# ETH_PCIE_CTRL.net
KiCad netlist of a schematic drawn in Altium Designer
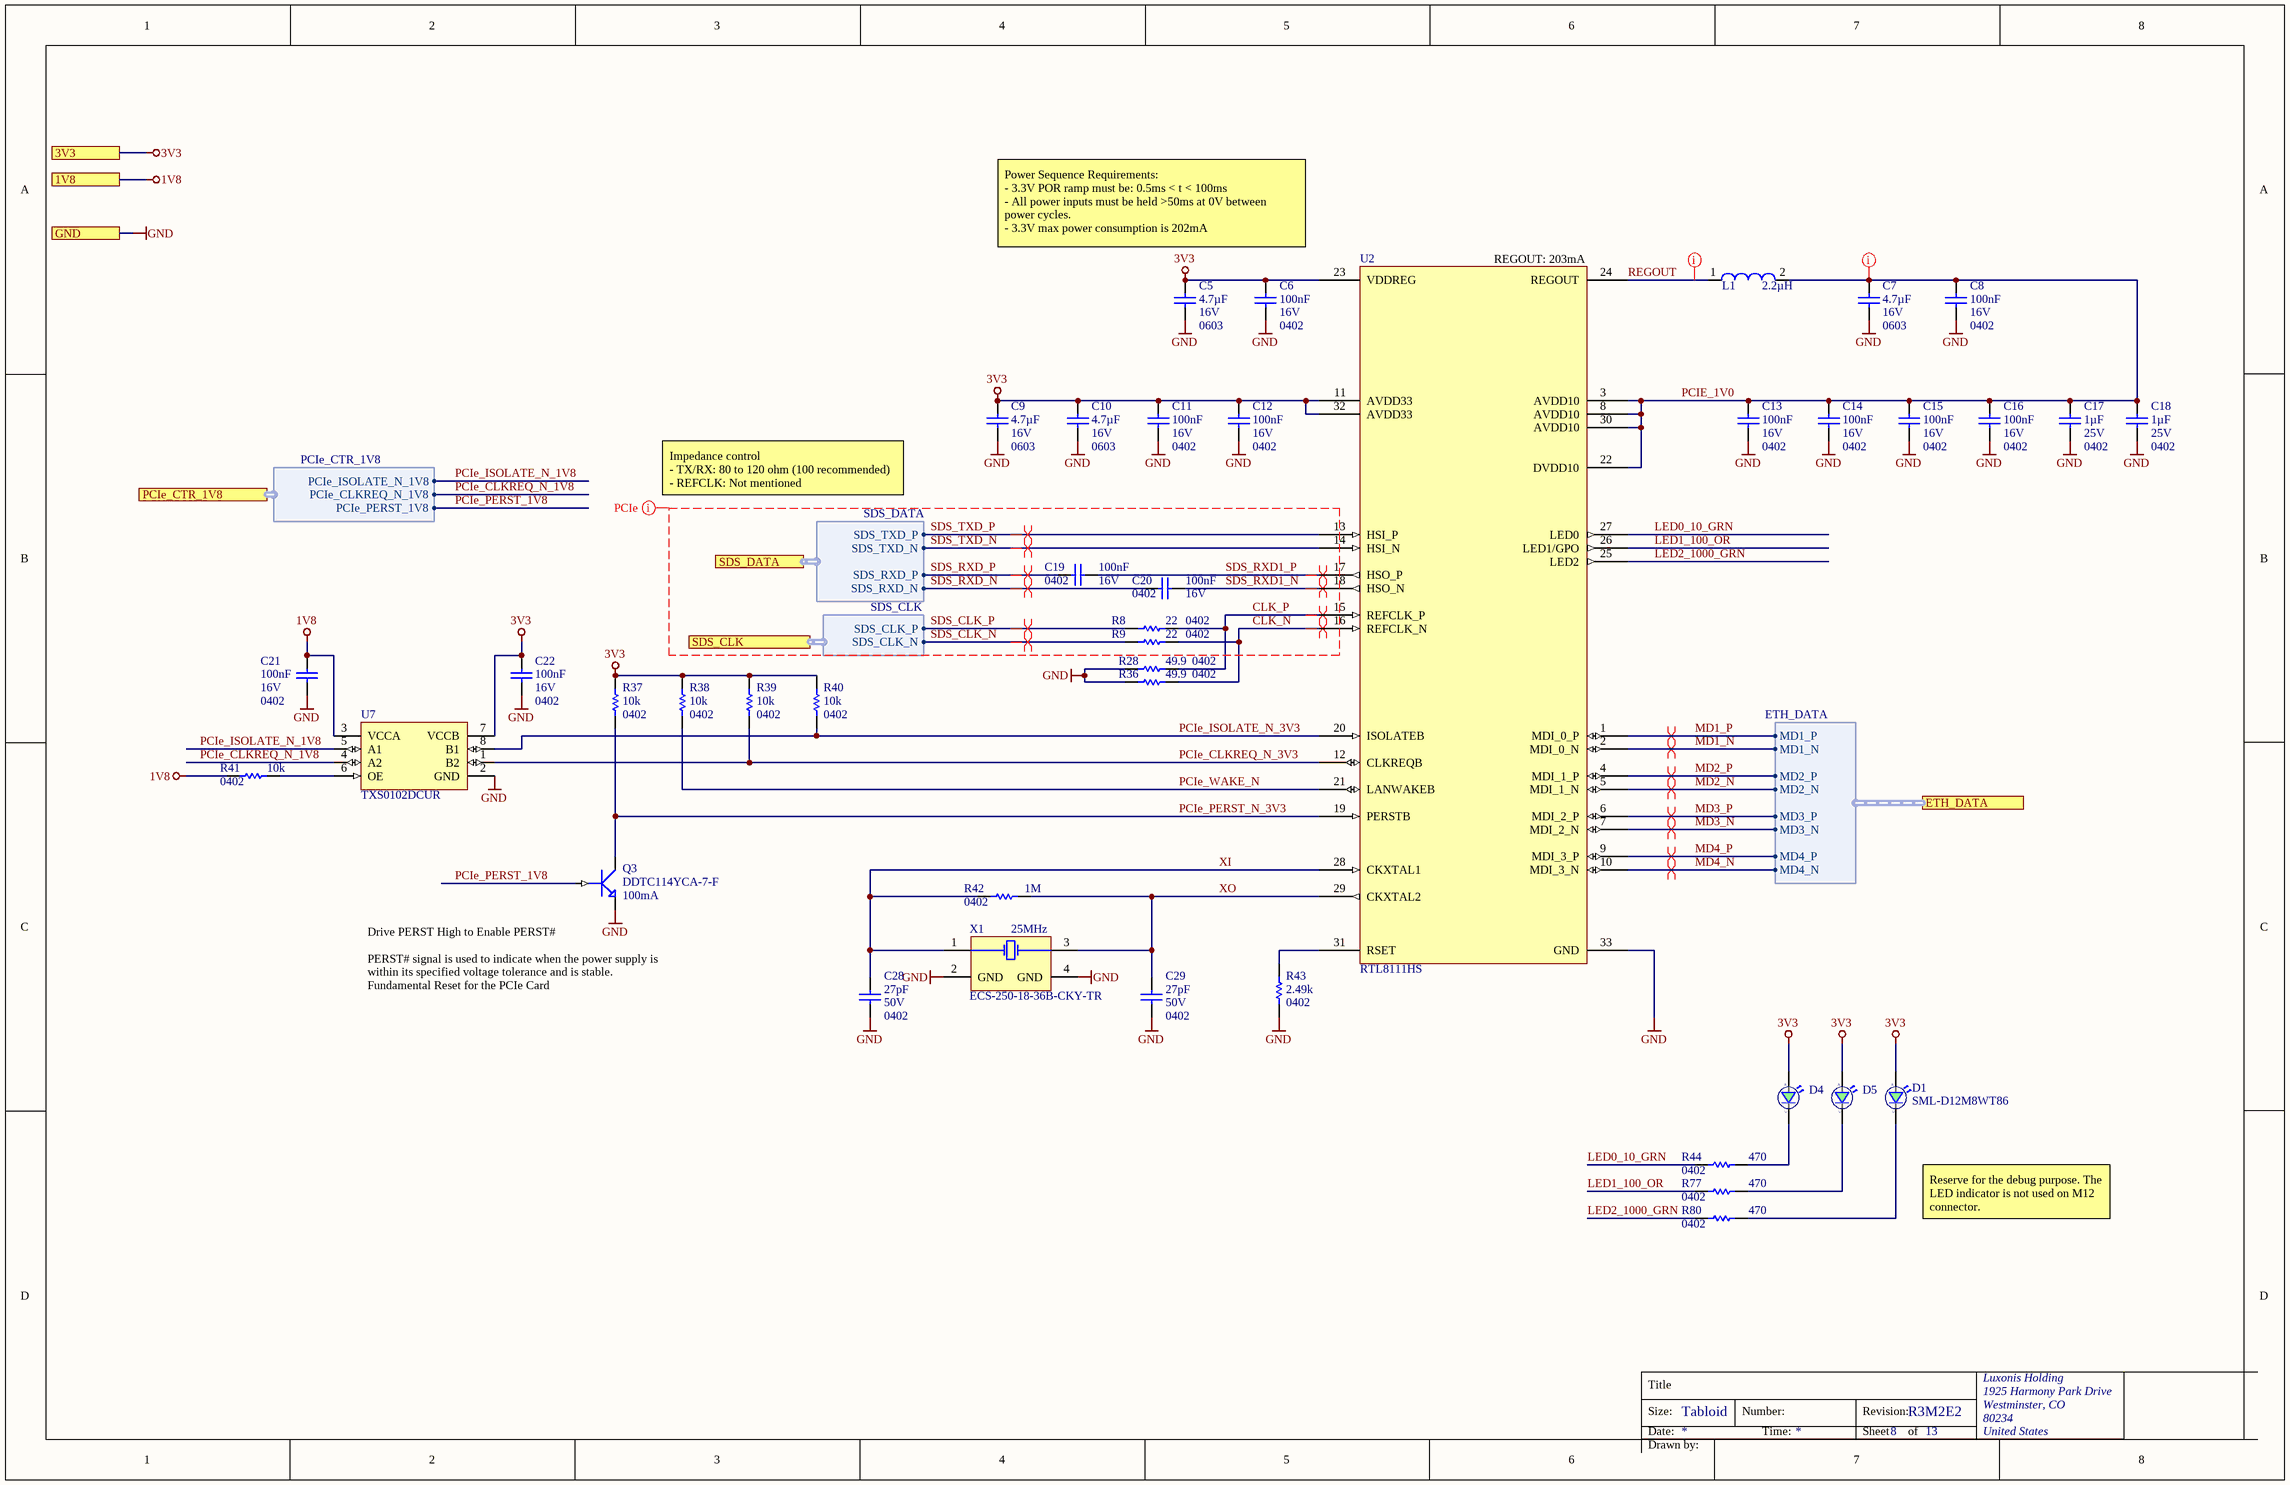
[diagram p0: ETH_PCIE_CTRL.SchDoc]

(export (version "E")
  (design (tool "Eeschema 10.0.6"))
  (components
    (comp (ref "C5")
      (value "4.7µF")
      (footprint "CAPC0603(1608)100_L")
      (description "CAP CER 4.7UF 16V X5R 0603 10%")
      (fields
        (field (name "VOLTAGE RATING") "16V")
        (field (name "CASE/PACKAGE") "0603")
        (field (name "TOLERANCE") "10%")
        (field (name "Comment") "GRM188R61C475KAAJD")
      )
      (libsource (lib "Luxonis LLC") (part "LLL153C70G474ME17E"))
    )
    (comp (ref "C6")
      (value "100nF")
      (footprint "CAPC0402(1005)60_L")
      (description "CAP CER 0.1UF 16V X7R 0402 10%")
      (fields
        (field (name "VOLTAGE RATING") "16V")
        (field (name "CASE/PACKAGE") "0402")
        (field (name "TOLERANCE") "10%")
        (field (name "Comment") "CL05B104KO5NFNC")
      )
      (libsource (lib "Luxonis LLC") (part "GRM188R61C475KAAJD"))
    )
    (comp (ref "C7")
      (value "4.7µF")
      (footprint "CAPC0603(1608)100_L")
      (description "CAP CER 4.7UF 16V X5R 0603 10%")
      (fields
        (field (name "VOLTAGE RATING") "16V")
        (field (name "CASE/PACKAGE") "0603")
        (field (name "TOLERANCE") "10%")
        (field (name "Comment") "GRM188R61C475KAAJD")
      )
      (libsource (lib "Luxonis LLC") (part "LLL153C70G474ME17E"))
    )
    (comp (ref "C8")
      (value "100nF")
      (footprint "CAPC0402(1005)60_L")
      (description "CAP CER 0.1UF 16V X7R 0402 10%")
      (fields
        (field (name "VOLTAGE RATING") "16V")
        (field (name "CASE/PACKAGE") "0402")
        (field (name "TOLERANCE") "10%")
        (field (name "Comment") "CL05B104KO5NFNC")
      )
      (libsource (lib "Luxonis LLC") (part "GRM188R61C475KAAJD"))
    )
    (comp (ref "C9")
      (value "4.7µF")
      (footprint "CAPC0603(1608)100_L")
      (description "CAP CER 4.7UF 16V X5R 0603 10%")
      (fields
        (field (name "VOLTAGE RATING") "16V")
        (field (name "CASE/PACKAGE") "0603")
        (field (name "TOLERANCE") "10%")
        (field (name "Comment") "GRM188R61C475KAAJD")
      )
      (libsource (lib "Luxonis LLC") (part "LLL153C70G474ME17E"))
    )
    (comp (ref "C10")
      (value "4.7µF")
      (footprint "CAPC0603(1608)100_L")
      (description "CAP CER 4.7UF 16V X5R 0603 10%")
      (fields
        (field (name "VOLTAGE RATING") "16V")
        (field (name "CASE/PACKAGE") "0603")
        (field (name "TOLERANCE") "10%")
        (field (name "Comment") "GRM188R61C475KAAJD")
      )
      (libsource (lib "Luxonis LLC") (part "LLL153C70G474ME17E"))
    )
    (comp (ref "C11")
      (value "100nF")
      (footprint "CAPC0402(1005)60_L")
      (description "CAP CER 0.1UF 16V X7R 0402 10%")
      (fields
        (field (name "VOLTAGE RATING") "16V")
        (field (name "CASE/PACKAGE") "0402")
        (field (name "TOLERANCE") "10%")
        (field (name "Comment") "CL05B104KO5NFNC")
      )
      (libsource (lib "Luxonis LLC") (part "GRM188R61C475KAAJD"))
    )
    (comp (ref "C12")
      (value "100nF")
      (footprint "CAPC0402(1005)60_L")
      (description "CAP CER 0.1UF 16V X7R 0402 10%")
      (fields
        (field (name "VOLTAGE RATING") "16V")
        (field (name "CASE/PACKAGE") "0402")
        (field (name "TOLERANCE") "10%")
        (field (name "Comment") "CL05B104KO5NFNC")
      )
      (libsource (lib "Luxonis LLC") (part "GRM188R61C475KAAJD"))
    )
    (comp (ref "C13")
      (value "100nF")
      (footprint "CAPC0402(1005)60_L")
      (description "CAP CER 0.1UF 16V X7R 0402 10%")
      (fields
        (field (name "VOLTAGE RATING") "16V")
        (field (name "CASE/PACKAGE") "0402")
        (field (name "TOLERANCE") "10%")
        (field (name "Comment") "CL05B104KO5NFNC")
      )
      (libsource (lib "Luxonis LLC") (part "GRM188R61C475KAAJD"))
    )
    (comp (ref "C14")
      (value "100nF")
      (footprint "CAPC0402(1005)60_L")
      (description "CAP CER 0.1UF 16V X7R 0402 10%")
      (fields
        (field (name "VOLTAGE RATING") "16V")
        (field (name "CASE/PACKAGE") "0402")
        (field (name "TOLERANCE") "10%")
        (field (name "Comment") "CL05B104KO5NFNC")
      )
      (libsource (lib "Luxonis LLC") (part "GRM188R61C475KAAJD"))
    )
    (comp (ref "C15")
      (value "100nF")
      (footprint "CAPC0402(1005)60_L")
      (description "CAP CER 0.1UF 16V X7R 0402 10%")
      (fields
        (field (name "VOLTAGE RATING") "16V")
        (field (name "CASE/PACKAGE") "0402")
        (field (name "TOLERANCE") "10%")
        (field (name "Comment") "CL05B104KO5NFNC")
      )
      (libsource (lib "Luxonis LLC") (part "GRM188R61C475KAAJD"))
    )
    (comp (ref "C16")
      (value "100nF")
      (footprint "CAPC0402(1005)60_L")
      (description "CAP CER 0.1UF 16V X7R 0402 10%")
      (fields
        (field (name "VOLTAGE RATING") "16V")
        (field (name "CASE/PACKAGE") "0402")
        (field (name "TOLERANCE") "10%")
        (field (name "Comment") "CL05B104KO5NFNC")
      )
      (libsource (lib "Luxonis LLC") (part "GRM188R61C475KAAJD"))
    )
    (comp (ref "C17")
      (value "1µF")
      (footprint "CAPC0402(1005)70_L")
      (description "CAP CER 1UF 25V X5R 0402 10%")
      (fields
        (field (name "VOLTAGE RATING") "25V")
        (field (name "CASE/PACKAGE") "0402")
        (field (name "TOLERANCE") "10%")
        (field (name "Comment") "GRM155R61E105KA12D")
      )
      (libsource (lib "Luxonis LLC") (part "GRM188R61C475KAAJD"))
    )
    (comp (ref "C18")
      (value "1µF")
      (footprint "CAPC0402(1005)70_L")
      (description "CAP CER 1UF 25V X5R 0402 10%")
      (fields
        (field (name "VOLTAGE RATING") "25V")
        (field (name "CASE/PACKAGE") "0402")
        (field (name "TOLERANCE") "10%")
        (field (name "Comment") "GRM155R61E105KA12D")
      )
      (libsource (lib "Luxonis LLC") (part "GRM188R61C475KAAJD"))
    )
    (comp (ref "C19")
      (value "100nF")
      (footprint "CAPC0402(1005)60_L")
      (description "CAP CER 0.1UF 16V X7R 0402 10%")
      (fields
        (field (name "VOLTAGE RATING") "16V")
        (field (name "CASE/PACKAGE") "0402")
        (field (name "TOLERANCE") "10%")
        (field (name "Comment") "CL05B104KO5NFNC")
      )
      (libsource (lib "Luxonis LLC") (part "GRM188R61C475KAAJD"))
    )
    (comp (ref "C20")
      (value "100nF")
      (footprint "CAPC0402(1005)60_L")
      (description "CAP CER 0.1UF 16V X7R 0402 10%")
      (fields
        (field (name "VOLTAGE RATING") "16V")
        (field (name "CASE/PACKAGE") "0402")
        (field (name "TOLERANCE") "10%")
        (field (name "Comment") "CL05B104KO5NFNC")
      )
      (libsource (lib "Luxonis LLC") (part "GRM188R61C475KAAJD"))
    )
    (comp (ref "C21")
      (value "100nF")
      (footprint "CAPC0402(1005)60_L")
      (description "CAP CER 0.1UF 16V X7R 0402 10%")
      (fields
        (field (name "VOLTAGE RATING") "16V")
        (field (name "CASE/PACKAGE") "0402")
        (field (name "TOLERANCE") "10%")
        (field (name "Comment") "CL05B104KO5NFNC")
      )
      (libsource (lib "Luxonis LLC") (part "GRM188R61C475KAAJD"))
    )
    (comp (ref "C22")
      (value "100nF")
      (footprint "CAPC0402(1005)60_L")
      (description "CAP CER 0.1UF 16V X7R 0402 10%")
      (fields
        (field (name "VOLTAGE RATING") "16V")
        (field (name "CASE/PACKAGE") "0402")
        (field (name "TOLERANCE") "10%")
        (field (name "Comment") "CL05B104KO5NFNC")
      )
      (libsource (lib "Luxonis LLC") (part "GRM188R61C475KAAJD"))
    )
    (comp (ref "C28")
      (value "27pF")
      (footprint "CAPC0402(1005)60_L")
      (description "CAP CER 27PF 50V C0G 0402 5%")
      (fields
        (field (name "VOLTAGE RATING") "50V")
        (field (name "TOLERANCE") "5%")
        (field (name "CASE/PACKAGE") "0402")
        (field (name "Comment") "C0402C270J5GACTU")
      )
      (libsource (lib "Luxonis LLC") (part "GRM188R61C475KAAJD"))
    )
    (comp (ref "C29")
      (value "27pF")
      (footprint "CAPC0402(1005)60_L")
      (description "CAP CER 27PF 50V C0G 0402 5%")
      (fields
        (field (name "VOLTAGE RATING") "50V")
        (field (name "TOLERANCE") "5%")
        (field (name "CASE/PACKAGE") "0402")
        (field (name "Comment") "C0402C270J5GACTU")
      )
      (libsource (lib "Luxonis LLC") (part "GRM188R61C475KAAJD"))
    )
    (comp (ref "D1")
      (value "SML-D12M8WT86")
      (footprint "SML_D1xx8W")
      (description "LED GREEN DIFFUSED 0603 SMD Green 572nm LED Indication - Discrete 2.2V 0603 (1608 Metric)")
      (libsource (lib "Luxonis LLC") (part "SML-D12M8WT86"))
    )
    (comp (ref "D4")
      (value "SML-D12M8WT86")
      (footprint "SML_D1xx8W")
      (description "LED GREEN DIFFUSED 0603 SMD Green 572nm LED Indication - Discrete 2.2V 0603 (1608 Metric)")
      (libsource (lib "Luxonis LLC") (part "SML-D12M8WT86"))
    )
    (comp (ref "D5")
      (value "SML-D12M8WT86")
      (footprint "SML_D1xx8W")
      (description "LED GREEN DIFFUSED 0603 SMD Green 572nm LED Indication - Discrete 2.2V 0603 (1608 Metric)")
      (libsource (lib "Luxonis LLC") (part "SML-D12M8WT86"))
    )
    (comp (ref "L1")
      (value "2.2µH")
      (footprint "LQH32NH2R2J23L")
      (description "Inductor Power Chip Wirewound 2.2uH 20% 100KHz Ferrite 1.6A 0.078Ohm DCR 1210 T/R")
      (fields (field (name "TOLERANCE") "20%") (field (name "Comment") "BRL3225T2R2M"))
      (libsource (lib "Luxonis LLC") (part "DFE252012P-1R0M=P2"))
    )
    (comp (ref "Q3")
      (value "DDTC114YCA-7-F")
      (footprint "DDTC114YCA-7-F-Footprint-1")
      (description "TRANS PREBIAS NPN 200MW SOT23-3")
      (fields (field (name "CONTINUOUS DRAIN CURRENT") "100mA"))
      (libsource (lib "Luxonis LLC") (part "DDTC114YCA-7-F"))
    )
    (comp (ref "R8")
      (value "22")
      (footprint "RESC0402(1005)_L")
      (description "RES SMD 22 OHM 1% 1/16W 0402")
      (fields
        (field (name "CASE/PACKAGE") "0402")
        (field (name "TOLERANCE") "1%")
        (field (name "Comment") "RC0402FR-0722RL")
      )
      (libsource (lib "Luxonis LLC") (part "Default resistor symbol"))
    )
    (comp (ref "R9")
      (value "22")
      (footprint "RESC0402(1005)_L")
      (description "RES SMD 22 OHM 1% 1/16W 0402")
      (fields
        (field (name "CASE/PACKAGE") "0402")
        (field (name "TOLERANCE") "1%")
        (field (name "Comment") "RC0402FR-0722RL")
      )
      (libsource (lib "Luxonis LLC") (part "Default resistor symbol"))
    )
    (comp (ref "R28")
      (value "49.9")
      (footprint "RESC0402(1005)_L")
      (description "RES SMD 49.9 OHM 1% 1/16W 0402")
      (fields
        (field (name "TOLERANCE") "1%")
        (field (name "CASE/PACKAGE") "0402")
        (field (name "Comment") "RC0402FR-0749R9L")
      )
      (libsource (lib "Luxonis LLC") (part "RC0402FR-0722RL_1"))
    )
    (comp (ref "R36")
      (value "49.9")
      (footprint "RESC0402(1005)_L")
      (description "RES SMD 49.9 OHM 1% 1/16W 0402")
      (fields
        (field (name "TOLERANCE") "1%")
        (field (name "CASE/PACKAGE") "0402")
        (field (name "Comment") "RC0402FR-0749R9L")
      )
      (libsource (lib "Luxonis LLC") (part "RC0402FR-0722RL_1"))
    )
    (comp (ref "R37")
      (value "10k")
      (footprint "RESC0402(1005)_L")
      (description "RES SMD 10K OHM 1% 1/16W 0402")
      (fields
        (field (name "CASE/PACKAGE") "0402")
        (field (name "TOLERANCE") "1%")
        (field (name "Comment") "RC0402FR-1310KL")
      )
      (libsource (lib "Luxonis LLC") (part "RC0402FR-0722RL_1"))
    )
    (comp (ref "R38")
      (value "10k")
      (footprint "RESC0402(1005)_L")
      (description "RES SMD 10K OHM 1% 1/16W 0402")
      (fields
        (field (name "CASE/PACKAGE") "0402")
        (field (name "TOLERANCE") "1%")
        (field (name "Comment") "RC0402FR-1310KL")
      )
      (libsource (lib "Luxonis LLC") (part "RC0402FR-0722RL_1"))
    )
    (comp (ref "R39")
      (value "10k")
      (footprint "RESC0402(1005)_L")
      (description "RES SMD 10K OHM 1% 1/16W 0402")
      (fields
        (field (name "CASE/PACKAGE") "0402")
        (field (name "TOLERANCE") "1%")
        (field (name "Comment") "RC0402FR-1310KL")
      )
      (libsource (lib "Luxonis LLC") (part "RC0402FR-0722RL_1"))
    )
    (comp (ref "R40")
      (value "10k")
      (footprint "RESC0402(1005)_L")
      (description "RES SMD 10K OHM 1% 1/16W 0402")
      (fields
        (field (name "CASE/PACKAGE") "0402")
        (field (name "TOLERANCE") "1%")
        (field (name "Comment") "RC0402FR-1310KL")
      )
      (libsource (lib "Luxonis LLC") (part "RC0402FR-0722RL_1"))
    )
    (comp (ref "R41")
      (value "10k")
      (footprint "RESC0402(1005)_L")
      (description "RES SMD 10K OHM 1% 1/16W 0402")
      (fields
        (field (name "CASE/PACKAGE") "0402")
        (field (name "TOLERANCE") "1%")
        (field (name "Comment") "RC0402FR-1310KL")
      )
      (libsource (lib "Luxonis LLC") (part "RC0402FR-0722RL_1"))
    )
    (comp (ref "R42")
      (value "1M")
      (footprint "RESC0402(1005)_L")
      (description "RES SMD 1M OHM 1% 1/16W 0402")
      (fields
        (field (name "CASE/PACKAGE") "0402")
        (field (name "TOLERANCE") "1%")
        (field (name "Comment") "RC0402FR-071ML")
      )
      (libsource (lib "Luxonis LLC") (part "Default resistor symbol"))
    )
    (comp (ref "R43")
      (value "2.49k")
      (footprint "RESC0402(1005)_L")
      (description "RES SMD 2.49K OHM 1% 1/16W 0402")
      (fields
        (field (name "CASE/PACKAGE") "0402")
        (field (name "TOLERANCE") "1%")
        (field (name "Comment") "RC0402FR-072K49L")
      )
      (libsource (lib "Luxonis LLC") (part "RC0402FR-0722RL_1"))
    )
    (comp (ref "R44")
      (value "470")
      (footprint "RESC0402(1005)_L")
      (description "RES SMD 470 OHM 1% 1/16W 0402")
      (fields
        (field (name "CASE/PACKAGE") "0402")
        (field (name "TOLERANCE") "1%")
        (field (name "Comment") "CRCW0402470RFKED")
      )
      (libsource (lib "Luxonis LLC") (part "Default resistor symbol"))
    )
    (comp (ref "R77")
      (value "470")
      (footprint "RESC0402(1005)_L")
      (description "RES SMD 470 OHM 1% 1/16W 0402")
      (fields
        (field (name "CASE/PACKAGE") "0402")
        (field (name "TOLERANCE") "1%")
        (field (name "Comment") "CRCW0402470RFKED")
      )
      (libsource (lib "Luxonis LLC") (part "Default resistor symbol"))
    )
    (comp (ref "R80")
      (value "470")
      (footprint "RESC0402(1005)_L")
      (description "RES SMD 470 OHM 1% 1/16W 0402")
      (fields
        (field (name "CASE/PACKAGE") "0402")
        (field (name "TOLERANCE") "1%")
        (field (name "Comment") "CRCW0402470RFKED")
      )
      (libsource (lib "Luxonis LLC") (part "Default resistor symbol"))
    )
    (comp (ref "U2")
      (value "RTL8111HS")
      (footprint "RTL8111Hx-CG")
      (description "IC ETHERNET/PCIe PHY Realtek")
      (libsource (lib "Luxonis LLC") (part "RTL8111HS"))
    )
    (comp (ref "U7")
      (value "TXS0102DCUR")
      (footprint "TXS0102DCUR")
      (description "TEXAS INSTRUMENTS - TXS0102DCUR - IC, TRANSLATOR, 2 BIT, BI, US-8")
      (libsource (lib "Luxonis LLC") (part "TXS0102DCUR"))
    )
    (comp (ref "X1")
      (value "ECS-250-18-36B-CKY-TR")
      (footprint "ECS-250-18-36B-CKY-TR")
      (description "CRYSTAL 25.0000MHZ 18PF SMD 25MHz ±10ppm Crystal 18pF 50 Ohms 4-SMD, No Lead")
      (fields (field (name "FREQUENCY") "25MHz"))
      (libsource (lib "Luxonis LLC") (part "ECS-250-18-36B-CKY-TR"))
    )
  )
  (nets
    (net (code "5") (name "/CLK_N") (class "Default")
      (node (ref "R36") (pin "2") (pinfunction "2_2") (pintype "passive"))
      (node (ref "R9") (pin "2") (pinfunction "2_2") (pintype "passive"))
      (node (ref "U2") (pin "16") (pinfunction "REFCLK_N_16") (pintype "input"))
    )
    (net (code "6") (name "/CLK_P") (class "Default")
      (node (ref "R28") (pin "2") (pinfunction "2_2") (pintype "passive"))
      (node (ref "R8") (pin "2") (pinfunction "2_2") (pintype "passive"))
      (node (ref "U2") (pin "15") (pinfunction "REFCLK_P_15") (pintype "input"))
    )
    (net (code "7") (name "/LED0_10_GRN") (class "Default")
      (node (ref "R44") (pin "1") (pinfunction "1_1") (pintype "passive"))
      (node (ref "U2") (pin "27") (pinfunction "LED0_27") (pintype "output"))
    )
    (net (code "8") (name "/LED1_100_OR") (class "Default")
      (node (ref "R77") (pin "1") (pinfunction "1_1") (pintype "passive"))
      (node (ref "U2") (pin "26") (pinfunction "LED1/GPO_26") (pintype "output"))
    )
    (net (code "9") (name "/LED2_1000_GRN") (class "Default")
      (node (ref "R80") (pin "1") (pinfunction "1_1") (pintype "passive"))
      (node (ref "U2") (pin "25") (pinfunction "LED2_25") (pintype "output"))
    )
    (net (code "10") (name "/MD1_N") (class "Default")
      (node (ref "U2") (pin "2") (pinfunction "MDI_0_N_2") (pintype "bidirectional"))
    )
    (net (code "11") (name "/MD1_P") (class "Default")
      (node (ref "U2") (pin "1") (pinfunction "MDI_0_P_1") (pintype "bidirectional"))
    )
    (net (code "12") (name "/MD2_N") (class "Default")
      (node (ref "U2") (pin "5") (pinfunction "MDI_1_N_5") (pintype "bidirectional"))
    )
    (net (code "13") (name "/MD2_P") (class "Default")
      (node (ref "U2") (pin "4") (pinfunction "MDI_1_P_4") (pintype "bidirectional"))
    )
    (net (code "14") (name "/MD3_N") (class "Default")
      (node (ref "U2") (pin "7") (pinfunction "MDI_2_N_7") (pintype "bidirectional"))
    )
    (net (code "15") (name "/MD3_P") (class "Default")
      (node (ref "U2") (pin "6") (pinfunction "MDI_2_P_6") (pintype "bidirectional"))
    )
    (net (code "16") (name "/MD4_N") (class "Default")
      (node (ref "U2") (pin "10") (pinfunction "MDI_3_N_10") (pintype "bidirectional"))
    )
    (net (code "17") (name "/MD4_P") (class "Default")
      (node (ref "U2") (pin "9") (pinfunction "MDI_3_P_9") (pintype "bidirectional"))
    )
    (net (code "18") (name "/PCIE_1V0") (class "Default")
      (node (ref "C13") (pin "2") (pinfunction "2_2") (pintype "passive"))
      (node (ref "C14") (pin "2") (pinfunction "2_2") (pintype "passive"))
      (node (ref "C15") (pin "2") (pinfunction "2_2") (pintype "passive"))
      (node (ref "C16") (pin "2") (pinfunction "2_2") (pintype "passive"))
      (node (ref "C17") (pin "2") (pinfunction "2_2") (pintype "passive"))
      (node (ref "C18") (pin "2") (pinfunction "2_2") (pintype "passive"))
      (node (ref "C7") (pin "2") (pinfunction "2_2") (pintype "passive"))
      (node (ref "C8") (pin "2") (pinfunction "2_2") (pintype "passive"))
      (node (ref "L1") (pin "2") (pinfunction "2_2") (pintype "passive"))
      (node (ref "U2") (pin "22") (pinfunction "DVDD10_22") (pintype "passive"))
      (node (ref "U2") (pin "3") (pinfunction "AVDD10_3") (pintype "passive"))
      (node (ref "U2") (pin "30") (pinfunction "AVDD10_30") (pintype "passive"))
      (node (ref "U2") (pin "8") (pinfunction "AVDD10_8") (pintype "passive"))
    )
    (net (code "19") (name "/PCIe_CLKREQ_N_1V8") (class "Default")
      (node (ref "U7") (pin "4") (pinfunction "A2_4") (pintype "bidirectional"))
    )
    (net (code "20") (name "/PCIe_CLKREQ_N_3V3") (class "Default")
      (node (ref "R39") (pin "1") (pinfunction "1_1") (pintype "passive"))
      (node (ref "U2") (pin "12") (pinfunction "CLKREQB_12") (pintype "bidirectional"))
      (node (ref "U7") (pin "1") (pinfunction "B2_1") (pintype "bidirectional"))
    )
    (net (code "21") (name "/PCIe_ISOLATE_N_1V8") (class "Default")
      (node (ref "U7") (pin "5") (pinfunction "A1_5") (pintype "bidirectional"))
    )
    (net (code "22") (name "/PCIe_ISOLATE_N_3V3") (class "Default")
      (node (ref "R40") (pin "1") (pinfunction "1_1") (pintype "passive"))
      (node (ref "U2") (pin "20") (pinfunction "ISOLATEB_20") (pintype "input"))
      (node (ref "U7") (pin "8") (pinfunction "B1_8") (pintype "bidirectional"))
    )
    (net (code "23") (name "/PCIe_PERST_1V8") (class "Default")
      (node (ref "Q3") (pin "1") (pinfunction "B_1") (pintype "input"))
    )
    (net (code "24") (name "/PCIe_PERST_N_3V3") (class "Default")
      (node (ref "Q3") (pin "3") (pinfunction "C_3") (pintype "passive"))
      (node (ref "R37") (pin "1") (pinfunction "1_1") (pintype "passive"))
      (node (ref "U2") (pin "19") (pinfunction "PERSTB_19") (pintype "input"))
    )
    (net (code "25") (name "/PCIe_WAKE_N") (class "Default")
      (node (ref "R38") (pin "1") (pinfunction "1_1") (pintype "passive"))
      (node (ref "U2") (pin "21") (pinfunction "LANWAKEB_21") (pintype "bidirectional"))
    )
    (net (code "26") (name "/REGOUT") (class "Default")
      (node (ref "L1") (pin "1") (pinfunction "1_1") (pintype "passive"))
      (node (ref "U2") (pin "24") (pinfunction "REGOUT_24") (pintype "passive"))
    )
    (net (code "27") (name "/SDS_CLK_N") (class "Default")
      (node (ref "R9") (pin "1") (pinfunction "1_1") (pintype "passive"))
    )
    (net (code "28") (name "/SDS_CLK_P") (class "Default")
      (node (ref "R8") (pin "1") (pinfunction "1_1") (pintype "passive"))
    )
    (net (code "29") (name "/SDS_RXD1_N") (class "Default")
      (node (ref "C20") (pin "1") (pinfunction "1_1") (pintype "passive"))
      (node (ref "U2") (pin "18") (pinfunction "HSO_N_18") (pintype "output"))
    )
    (net (code "30") (name "/SDS_RXD1_P") (class "Default")
      (node (ref "C19") (pin "1") (pinfunction "1_1") (pintype "passive"))
      (node (ref "U2") (pin "17") (pinfunction "HSO_P_17") (pintype "output"))
    )
    (net (code "31") (name "/SDS_RXD_N") (class "Default")
      (node (ref "C20") (pin "2") (pinfunction "2_2") (pintype "passive"))
    )
    (net (code "32") (name "/SDS_RXD_P") (class "Default")
      (node (ref "C19") (pin "2") (pinfunction "2_2") (pintype "passive"))
    )
    (net (code "33") (name "/SDS_TXD_N") (class "Default")
      (node (ref "U2") (pin "14") (pinfunction "HSI_N_14") (pintype "input"))
    )
    (net (code "34") (name "/SDS_TXD_P") (class "Default")
      (node (ref "U2") (pin "13") (pinfunction "HSI_P_13") (pintype "input"))
    )
    (net (code "35") (name "/XI") (class "Default")
      (node (ref "C28") (pin "2") (pinfunction "2_2") (pintype "passive"))
      (node (ref "R42") (pin "1") (pinfunction "1_1") (pintype "passive"))
      (node (ref "U2") (pin "28") (pinfunction "CKXTAL1_28") (pintype "input"))
      (node (ref "X1") (pin "1") (pinfunction "X1_1") (pintype "passive"))
    )
    (net (code "36") (name "/XO") (class "Default")
      (node (ref "C29") (pin "2") (pinfunction "2_2") (pintype "passive"))
      (node (ref "R42") (pin "2") (pinfunction "2_2") (pintype "passive"))
      (node (ref "U2") (pin "29") (pinfunction "CKXTAL2_29") (pintype "output"))
      (node (ref "X1") (pin "3") (pinfunction "X2_3") (pintype "passive"))
    )
    (net (code "41") (name "1V8") (class "Default")
      (node (ref "C21") (pin "2") (pinfunction "2_2") (pintype "passive"))
      (node (ref "R41") (pin "1") (pinfunction "1_1") (pintype "passive"))
      (node (ref "U7") (pin "3") (pinfunction "VCCA_3") (pintype "power_in"))
    )
    (net (code "42") (name "3V3") (class "Default")
      (node (ref "C10") (pin "2") (pinfunction "2_2") (pintype "passive"))
      (node (ref "C11") (pin "2") (pinfunction "2_2") (pintype "passive"))
      (node (ref "C12") (pin "2") (pinfunction "2_2") (pintype "passive"))
      (node (ref "C22") (pin "2") (pinfunction "2_2") (pintype "passive"))
      (node (ref "C5") (pin "2") (pinfunction "2_2") (pintype "passive"))
      (node (ref "C6") (pin "2") (pinfunction "2_2") (pintype "passive"))
      (node (ref "C9") (pin "2") (pinfunction "2_2") (pintype "passive"))
      (node (ref "D1") (pin "2") (pinfunction "A_2") (pintype "passive"))
      (node (ref "D4") (pin "2") (pinfunction "A_2") (pintype "passive"))
      (node (ref "D5") (pin "2") (pinfunction "A_2") (pintype "passive"))
      (node (ref "R37") (pin "2") (pinfunction "2_2") (pintype "passive"))
      (node (ref "R38") (pin "2") (pinfunction "2_2") (pintype "passive"))
      (node (ref "R39") (pin "2") (pinfunction "2_2") (pintype "passive"))
      (node (ref "R40") (pin "2") (pinfunction "2_2") (pintype "passive"))
      (node (ref "U2") (pin "11") (pinfunction "AVDD33_11") (pintype "passive"))
      (node (ref "U2") (pin "23") (pinfunction "VDDREG_23") (pintype "passive"))
      (node (ref "U2") (pin "32") (pinfunction "AVDD33_32") (pintype "passive"))
      (node (ref "U7") (pin "7") (pinfunction "VCCB_7") (pintype "power_in"))
    )
    (net (code "43") (name "GND") (class "Default")
      (node (ref "C10") (pin "1") (pinfunction "1_1") (pintype "passive"))
      (node (ref "C11") (pin "1") (pinfunction "1_1") (pintype "passive"))
      (node (ref "C12") (pin "1") (pinfunction "1_1") (pintype "passive"))
      (node (ref "C13") (pin "1") (pinfunction "1_1") (pintype "passive"))
      (node (ref "C14") (pin "1") (pinfunction "1_1") (pintype "passive"))
      (node (ref "C15") (pin "1") (pinfunction "1_1") (pintype "passive"))
      (node (ref "C16") (pin "1") (pinfunction "1_1") (pintype "passive"))
      (node (ref "C17") (pin "1") (pinfunction "1_1") (pintype "passive"))
      (node (ref "C18") (pin "1") (pinfunction "1_1") (pintype "passive"))
      (node (ref "C21") (pin "1") (pinfunction "1_1") (pintype "passive"))
      (node (ref "C22") (pin "1") (pinfunction "1_1") (pintype "passive"))
      (node (ref "C28") (pin "1") (pinfunction "1_1") (pintype "passive"))
      (node (ref "C29") (pin "1") (pinfunction "1_1") (pintype "passive"))
      (node (ref "C5") (pin "1") (pinfunction "1_1") (pintype "passive"))
      (node (ref "C6") (pin "1") (pinfunction "1_1") (pintype "passive"))
      (node (ref "C7") (pin "1") (pinfunction "1_1") (pintype "passive"))
      (node (ref "C8") (pin "1") (pinfunction "1_1") (pintype "passive"))
      (node (ref "C9") (pin "1") (pinfunction "1_1") (pintype "passive"))
      (node (ref "Q3") (pin "2") (pinfunction "E_2") (pintype "passive"))
      (node (ref "R28") (pin "1") (pinfunction "1_1") (pintype "passive"))
      (node (ref "R36") (pin "1") (pinfunction "1_1") (pintype "passive"))
      (node (ref "R43") (pin "1") (pinfunction "1_1") (pintype "passive"))
      (node (ref "U2") (pin "33") (pinfunction "GND_33") (pintype "passive"))
      (node (ref "U7") (pin "2") (pinfunction "GND_2") (pintype "power_in"))
      (node (ref "X1") (pin "2") (pinfunction "GND_2") (pintype "power_in"))
      (node (ref "X1") (pin "4") (pinfunction "GND_4") (pintype "power_in"))
    )
    (net (code "44") (name "Net-(D1-C)") (class "Default")
      (node (ref "D1") (pin "1") (pinfunction "C_1") (pintype "passive"))
      (node (ref "R80") (pin "2") (pinfunction "2_2") (pintype "passive"))
    )
    (net (code "45") (name "Net-(D4-C)") (class "Default")
      (node (ref "D4") (pin "1") (pinfunction "C_1") (pintype "passive"))
      (node (ref "R44") (pin "2") (pinfunction "2_2") (pintype "passive"))
    )
    (net (code "46") (name "Net-(D5-C)") (class "Default")
      (node (ref "D5") (pin "1") (pinfunction "C_1") (pintype "passive"))
      (node (ref "R77") (pin "2") (pinfunction "2_2") (pintype "passive"))
    )
    (net (code "47") (name "Net-(U2-RSET)") (class "Default")
      (node (ref "R43") (pin "2") (pinfunction "2_2") (pintype "passive"))
      (node (ref "U2") (pin "31") (pinfunction "RSET_31") (pintype "passive"))
    )
    (net (code "48") (name "Net-(U7-OE)") (class "Default")
      (node (ref "R41") (pin "2") (pinfunction "2_2") (pintype "passive"))
      (node (ref "U7") (pin "6") (pinfunction "OE_6") (pintype "input"))
    )
  )
)
